# EasyEDA.net
KiCad netlist of a schematic drawn in EasyEDA
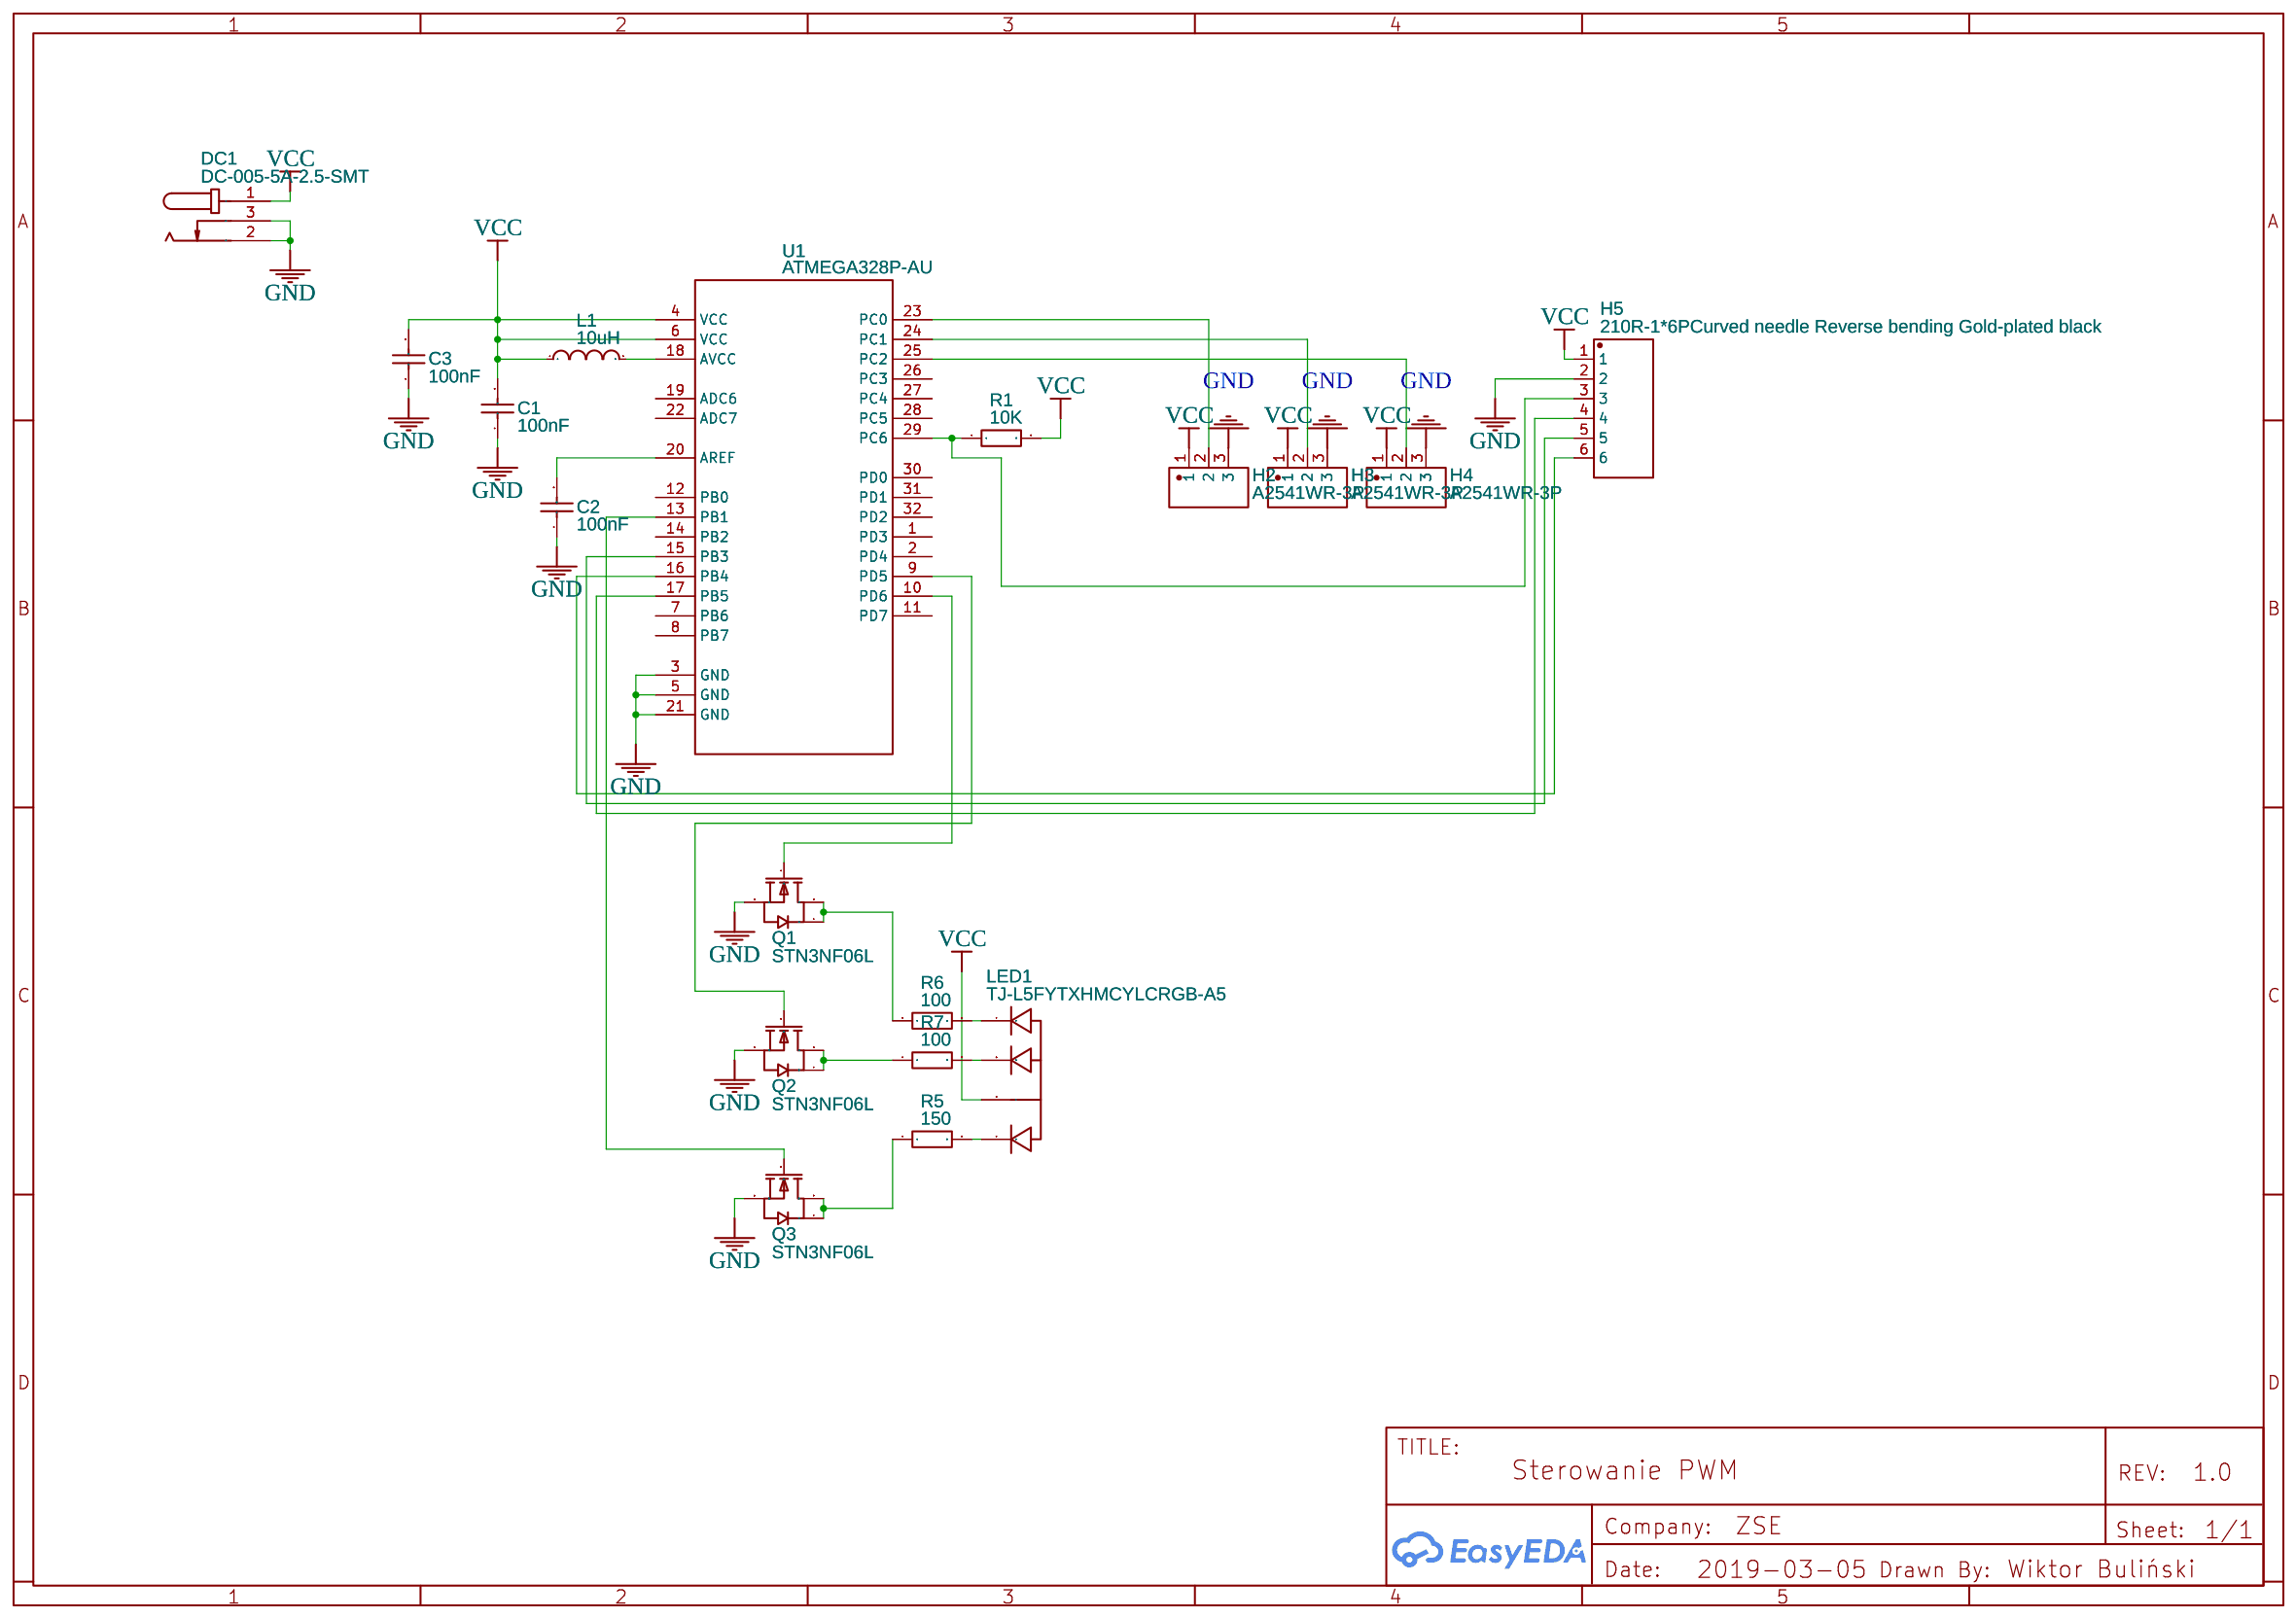
[diagram p0: schematic sheet]

(export (version "E")
  (design (tool "Eeschema 10.0.6"))
  (components
    (comp (ref "C1")
      (value "100nF")
      (fields
        (field (name "BOM_Manufacturer Part") "CC1206KKX7R0BB104")
        (field (name "BOM_Supplier Part") "C107181")
      )
      (libsource (lib "") (part "CC1206KKX7R0BB104"))
    )
    (comp (ref "C2")
      (value "100nF")
      (fields
        (field (name "BOM_Manufacturer Part") "CC1206KKX7R0BB104")
        (field (name "BOM_Supplier Part") "C107181")
      )
      (libsource (lib "") (part "CC1206KKX7R0BB104"))
    )
    (comp (ref "C3")
      (value "100nF")
      (fields
        (field (name "BOM_Manufacturer Part") "CC1206KKX7R0BB104")
        (field (name "BOM_Supplier Part") "C107181")
      )
      (libsource (lib "") (part "CC1206KKX7R0BB104"))
    )
    (comp (ref "DC1")
      (value "DC-005-5A-2.5-SMT")
      (fields (field (name "BOM_Supplier Part") "C319133"))
      (libsource (lib "") (part "Unknown_100_105"))
    )
    (comp (ref "H2")
      (value "A2541WR-3P")
      (fields (field (name "BOM_Supplier Part") "C225489"))
      (libsource (lib "") (part "Unknown_605_235"))
    )
    (comp (ref "H3")
      (value "A2541WR-3P")
      (fields (field (name "BOM_Supplier Part") "C225489"))
      (libsource (lib "") (part "Unknown_655_235"))
    )
    (comp (ref "H4")
      (value "A2541WR-3P")
      (fields (field (name "BOM_Supplier Part") "C225489"))
      (libsource (lib "") (part "Unknown_705_235"))
    )
    (comp (ref "H5")
      (value "210R-1*6PCurved needle Reverse bending Gold-plated black")
      (fields (field (name "BOM_Supplier Part") "C124367"))
      (libsource (lib "") (part "Unknown_810_200"))
    )
    (comp (ref "L1")
      (value "10uH")
      (fields
        (field (name "BOM_Manufacturer Part") "CMP321609XD100KT")
        (field (name "BOM_Supplier Part") "C139251")
      )
      (libsource (lib "") (part "CMP321609XD100KT"))
    )
    (comp (ref "LED1")
      (value "TJ-L5FYTXHMCYLCRGB-A5")
      (fields (field (name "BOM_Supplier Part") "C331057"))
      (libsource (lib "") (part "Unknown_510_540"))
    )
    (comp (ref "Q1")
      (value "STN3NF06L")
      (fields (field (name "BOM_Supplier Part") "C222218"))
      (libsource (lib "") (part "Unknown_390_450"))
    )
    (comp (ref "Q2")
      (value "STN3NF06L")
      (fields (field (name "BOM_Supplier Part") "C222218"))
      (libsource (lib "") (part "Unknown_390_525"))
    )
    (comp (ref "Q3")
      (value "STN3NF06L")
      (fields (field (name "BOM_Supplier Part") "C222218"))
      (libsource (lib "") (part "Unknown_390_600"))
    )
    (comp (ref "R1")
      (value "10K")
      (fields
        (field (name "BOM_Manufacturer Part") "1206W4F1002T5E")
        (field (name "BOM_Supplier Part") "C17902")
      )
      (libsource (lib "") (part "1206W4F1002T5E"))
    )
    (comp (ref "R5")
      (value "150")
      (fields
        (field (name "BOM_Manufacturer Part") "1206W4F1500T5E")
        (field (name "BOM_Supplier Part") "C17917")
      )
      (libsource (lib "") (part "1206W4F1500T5E"))
    )
    (comp (ref "R6")
      (value "100")
      (fields
        (field (name "BOM_Manufacturer Part") "AR06DTCV1000")
        (field (name "BOM_Supplier Part") "C319959")
      )
      (libsource (lib "") (part "AR06DTCV1000"))
    )
    (comp (ref "R7")
      (value "100")
      (fields
        (field (name "BOM_Manufacturer Part") "AR06DTCV1000")
        (field (name "BOM_Supplier Part") "C319959")
      )
      (libsource (lib "") (part "AR06DTCV1000"))
    )
    (comp (ref "U1")
      (value "ATMEGA328P-AU")
      (fields (field (name "BOM_Supplier Part") "C14877"))
      (libsource (lib "") (part "Unknown_395_255"))
    )
  )
  (nets
    (net (code "1") (name "GND") (class "Default")
      (node (ref "C1") (pin "1") (pinfunction "1_1") (pintype "input"))
      (node (ref "C2") (pin "1") (pinfunction "1_1") (pintype "input"))
      (node (ref "C3") (pin "1") (pinfunction "1_1") (pintype "input"))
      (node (ref "DC1") (pin "2") (pinfunction "2_2") (pintype "unspecified"))
      (node (ref "DC1") (pin "3") (pinfunction "3_3") (pintype "unspecified"))
      (node (ref "H2") (pin "3") (pinfunction "3_3") (pintype "unspecified"))
      (node (ref "H3") (pin "3") (pinfunction "3_3") (pintype "unspecified"))
      (node (ref "H4") (pin "3") (pinfunction "3_3") (pintype "unspecified"))
      (node (ref "H5") (pin "2") (pinfunction "2_2") (pintype "unspecified"))
      (node (ref "Q1") (pin "3") (pinfunction "S_3") (pintype "unspecified"))
      (node (ref "Q2") (pin "3") (pinfunction "S_3") (pintype "unspecified"))
      (node (ref "Q3") (pin "3") (pinfunction "S_3") (pintype "unspecified"))
      (node (ref "U1") (pin "21") (pinfunction "GND_21") (pintype "unspecified"))
      (node (ref "U1") (pin "3") (pinfunction "GND_3") (pintype "unspecified"))
      (node (ref "U1") (pin "5") (pinfunction "GND_5") (pintype "unspecified"))
    )
    (net (code "2") (name "Net-(LED1-Pad1)") (class "Default")
      (node (ref "LED1") (pin "1") (pinfunction "1_1") (pintype "unspecified"))
      (node (ref "R5") (pin "2") (pinfunction "2_2") (pintype "input"))
    )
    (net (code "3") (name "Net-(LED1-Pad3)") (class "Default")
      (node (ref "LED1") (pin "3") (pinfunction "3_3") (pintype "unspecified"))
      (node (ref "R7") (pin "2") (pinfunction "2_2") (pintype "unspecified"))
    )
    (net (code "4") (name "Net-(LED1-Pad4)") (class "Default")
      (node (ref "LED1") (pin "4") (pinfunction "4_4") (pintype "unspecified"))
      (node (ref "R6") (pin "2") (pinfunction "2_2") (pintype "unspecified"))
    )
    (net (code "5") (name "Net-(Q1-D-Pad2)") (class "Default")
      (node (ref "Q1") (pin "2") (pinfunction "D_2") (pintype "unspecified"))
      (node (ref "Q1") (pin "4") (pinfunction "D_4") (pintype "unspecified"))
      (node (ref "R6") (pin "1") (pinfunction "1_1") (pintype "unspecified"))
    )
    (net (code "6") (name "Net-(Q1-G)") (class "Default")
      (node (ref "Q1") (pin "1") (pinfunction "G_1") (pintype "unspecified"))
      (node (ref "U1") (pin "10") (pinfunction "PD6_10") (pintype "unspecified"))
    )
    (net (code "7") (name "Net-(Q2-D-Pad2)") (class "Default")
      (node (ref "Q2") (pin "2") (pinfunction "D_2") (pintype "unspecified"))
      (node (ref "Q2") (pin "4") (pinfunction "D_4") (pintype "unspecified"))
      (node (ref "R7") (pin "1") (pinfunction "1_1") (pintype "unspecified"))
    )
    (net (code "8") (name "Net-(Q2-G)") (class "Default")
      (node (ref "Q2") (pin "1") (pinfunction "G_1") (pintype "unspecified"))
      (node (ref "U1") (pin "9") (pinfunction "PD5_9") (pintype "unspecified"))
    )
    (net (code "9") (name "Net-(Q3-D-Pad2)") (class "Default")
      (node (ref "Q3") (pin "2") (pinfunction "D_2") (pintype "unspecified"))
      (node (ref "Q3") (pin "4") (pinfunction "D_4") (pintype "unspecified"))
      (node (ref "R5") (pin "1") (pinfunction "1_1") (pintype "input"))
    )
    (net (code "10") (name "Net-(Q3-G)") (class "Default")
      (node (ref "Q3") (pin "1") (pinfunction "G_1") (pintype "unspecified"))
      (node (ref "U1") (pin "13") (pinfunction "PB1_13") (pintype "unspecified"))
    )
    (net (code "11") (name "Net-(U1-AREF)") (class "Default")
      (node (ref "C2") (pin "2") (pinfunction "2_2") (pintype "input"))
      (node (ref "U1") (pin "20") (pinfunction "AREF_20") (pintype "input"))
    )
    (net (code "12") (name "Net-(U1-AVCC)") (class "Default")
      (node (ref "L1") (pin "2") (pinfunction "2_2") (pintype "unspecified"))
      (node (ref "U1") (pin "18") (pinfunction "AVCC_18") (pintype "passive"))
    )
    (net (code "13") (name "Net-(U1-PB3)") (class "Default")
      (node (ref "H5") (pin "5") (pinfunction "5_5") (pintype "unspecified"))
      (node (ref "U1") (pin "15") (pinfunction "PB3_15") (pintype "unspecified"))
    )
    (net (code "14") (name "Net-(U1-PB4)") (class "Default")
      (node (ref "H5") (pin "6") (pinfunction "6_6") (pintype "unspecified"))
      (node (ref "U1") (pin "16") (pinfunction "PB4_16") (pintype "unspecified"))
    )
    (net (code "15") (name "Net-(U1-PB5)") (class "Default")
      (node (ref "H5") (pin "4") (pinfunction "4_4") (pintype "unspecified"))
      (node (ref "U1") (pin "17") (pinfunction "PB5_17") (pintype "unspecified"))
    )
    (net (code "16") (name "Net-(U1-PC0)") (class "Default")
      (node (ref "H2") (pin "2") (pinfunction "2_2") (pintype "unspecified"))
      (node (ref "U1") (pin "23") (pinfunction "PC0_23") (pintype "unspecified"))
    )
    (net (code "17") (name "Net-(U1-PC1)") (class "Default")
      (node (ref "H3") (pin "2") (pinfunction "2_2") (pintype "unspecified"))
      (node (ref "U1") (pin "24") (pinfunction "PC1_24") (pintype "unspecified"))
    )
    (net (code "18") (name "Net-(U1-PC2)") (class "Default")
      (node (ref "H4") (pin "2") (pinfunction "2_2") (pintype "unspecified"))
      (node (ref "U1") (pin "25") (pinfunction "PC2_25") (pintype "unspecified"))
    )
    (net (code "19") (name "Net-(U1-PC6)") (class "Default")
      (node (ref "H5") (pin "3") (pinfunction "3_3") (pintype "unspecified"))
      (node (ref "R1") (pin "1") (pinfunction "1_1") (pintype "input"))
      (node (ref "U1") (pin "29") (pinfunction "PC6_29") (pintype "unspecified"))
    )
    (net (code "20") (name "VCC") (class "Default")
      (node (ref "C1") (pin "2") (pinfunction "2_2") (pintype "input"))
      (node (ref "C3") (pin "2") (pinfunction "2_2") (pintype "input"))
      (node (ref "DC1") (pin "1") (pinfunction "1_1") (pintype "unspecified"))
      (node (ref "H2") (pin "1") (pinfunction "1_1") (pintype "unspecified"))
      (node (ref "H3") (pin "1") (pinfunction "1_1") (pintype "unspecified"))
      (node (ref "H4") (pin "1") (pinfunction "1_1") (pintype "unspecified"))
      (node (ref "H5") (pin "1") (pinfunction "1_1") (pintype "unspecified"))
      (node (ref "L1") (pin "1") (pinfunction "1_1") (pintype "unspecified"))
      (node (ref "LED1") (pin "2") (pinfunction "+_2") (pintype "unspecified"))
      (node (ref "R1") (pin "2") (pinfunction "2_2") (pintype "input"))
      (node (ref "U1") (pin "4") (pinfunction "VCC_4") (pintype "passive"))
      (node (ref "U1") (pin "6") (pinfunction "VCC_6") (pintype "passive"))
    )
    (net (code "21") (name "unconnected-(U1-ADC6-Pad19)") (class "Default")
      (node (ref "U1") (pin "19") (pinfunction "ADC6_19") (pintype "input"))
    )
    (net (code "22") (name "unconnected-(U1-ADC7-Pad22)") (class "Default")
      (node (ref "U1") (pin "22") (pinfunction "ADC7_22") (pintype "input"))
    )
    (net (code "23") (name "unconnected-(U1-PB0-Pad12)") (class "Default")
      (node (ref "U1") (pin "12") (pinfunction "PB0_12") (pintype "unspecified"))
    )
    (net (code "24") (name "unconnected-(U1-PB2-Pad14)") (class "Default")
      (node (ref "U1") (pin "14") (pinfunction "PB2_14") (pintype "unspecified"))
    )
    (net (code "25") (name "unconnected-(U1-PB6-Pad7)") (class "Default")
      (node (ref "U1") (pin "7") (pinfunction "PB6_7") (pintype "unspecified"))
    )
    (net (code "26") (name "unconnected-(U1-PB7-Pad8)") (class "Default")
      (node (ref "U1") (pin "8") (pinfunction "PB7_8") (pintype "unspecified"))
    )
    (net (code "27") (name "unconnected-(U1-PC3-Pad26)") (class "Default")
      (node (ref "U1") (pin "26") (pinfunction "PC3_26") (pintype "unspecified"))
    )
    (net (code "28") (name "unconnected-(U1-PC4-Pad27)") (class "Default")
      (node (ref "U1") (pin "27") (pinfunction "PC4_27") (pintype "unspecified"))
    )
    (net (code "29") (name "unconnected-(U1-PC5-Pad28)") (class "Default")
      (node (ref "U1") (pin "28") (pinfunction "PC5_28") (pintype "unspecified"))
    )
    (net (code "30") (name "unconnected-(U1-PD0-Pad30)") (class "Default")
      (node (ref "U1") (pin "30") (pinfunction "PD0_30") (pintype "unspecified"))
    )
    (net (code "31") (name "unconnected-(U1-PD1-Pad31)") (class "Default")
      (node (ref "U1") (pin "31") (pinfunction "PD1_31") (pintype "unspecified"))
    )
    (net (code "32") (name "unconnected-(U1-PD2-Pad32)") (class "Default")
      (node (ref "U1") (pin "32") (pinfunction "PD2_32") (pintype "unspecified"))
    )
    (net (code "33") (name "unconnected-(U1-PD3-Pad1)") (class "Default")
      (node (ref "U1") (pin "1") (pinfunction "PD3_1") (pintype "unspecified"))
    )
    (net (code "34") (name "unconnected-(U1-PD4-Pad2)") (class "Default")
      (node (ref "U1") (pin "2") (pinfunction "PD4_2") (pintype "unspecified"))
    )
    (net (code "35") (name "unconnected-(U1-PD7-Pad11)") (class "Default")
      (node (ref "U1") (pin "11") (pinfunction "PD7_11") (pintype "unspecified"))
    )
  )
)
